# PLD_Connectors_PC-104.net
KiCad netlist of a schematic drawn in Altium Designer
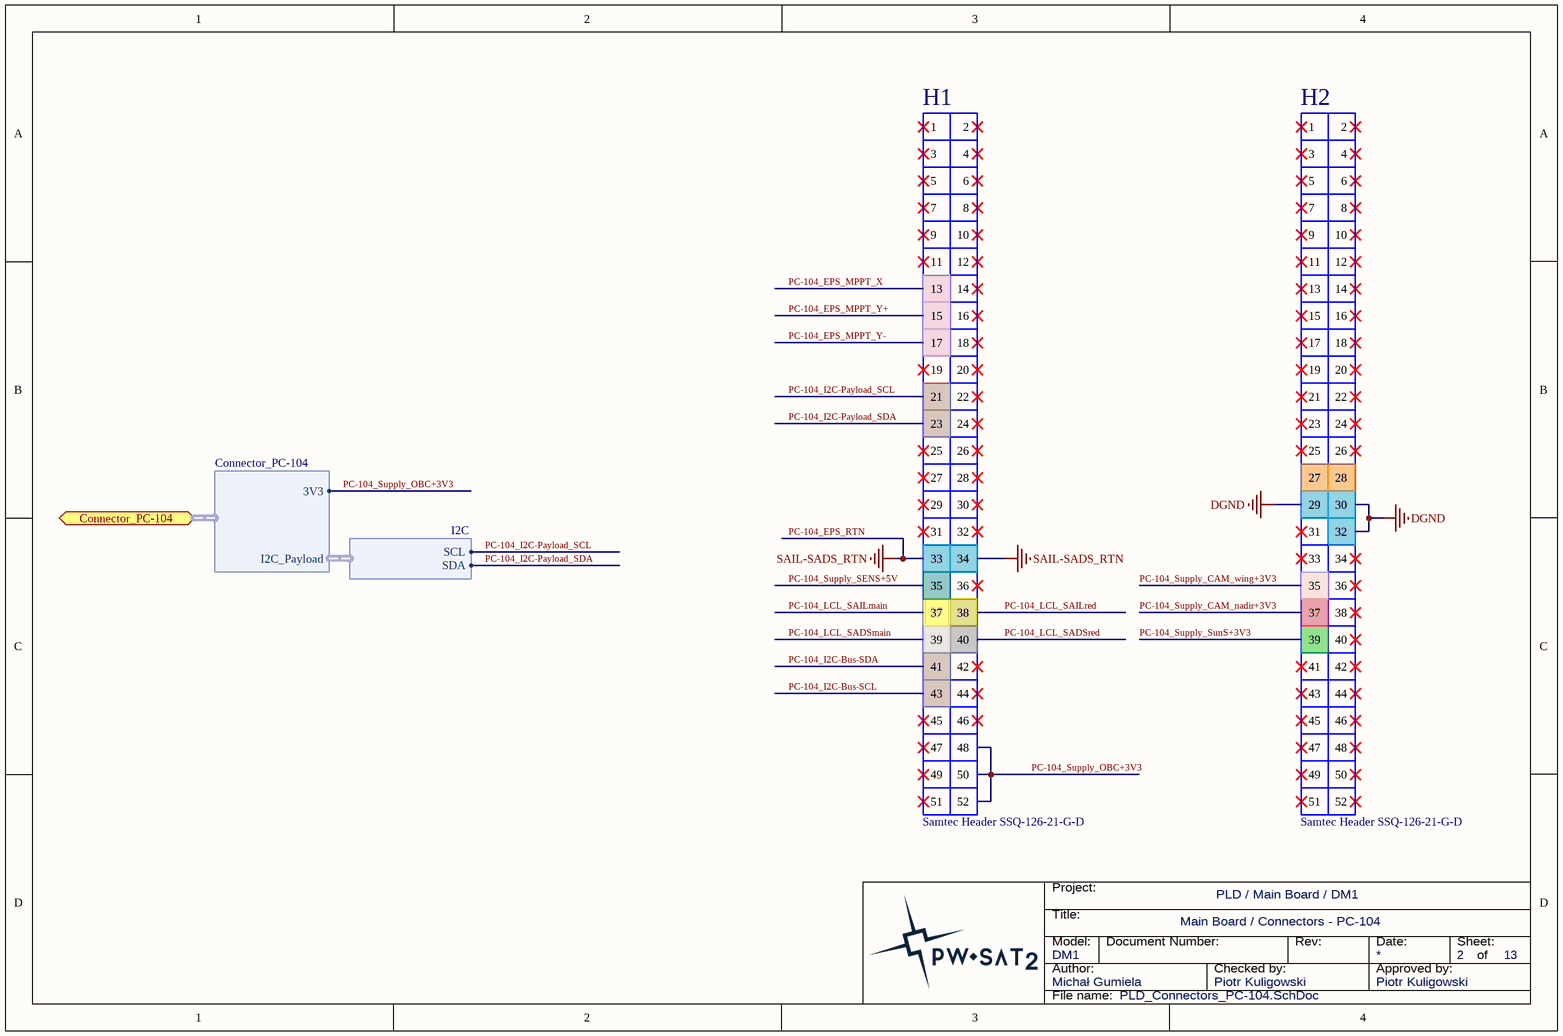
[diagram p0: PLD_Connectors_PC-104.SchDoc]

(export (version "E")
  (design (tool "Eeschema 10.0.6"))
  (components
    (comp (ref "H1")
      (value "Samtec Header SSQ-126-21-G-D")
      (footprint "Samtec_SSQ-126-21-G-D")
      (description "Samtec SSQ Series Header , 2.54mm pitch, 2x26pin. PC-104 Stack Connector.")
      (libsource (lib "connectors_printed-circuit-board") (part "Samtec_SSQ-126-xx-x-D"))
    )
    (comp (ref "H2")
      (value "Samtec Header SSQ-126-21-G-D")
      (footprint "Samtec_SSQ-126-21-G-D")
      (description "Samtec SSQ Series Header , 2.54mm pitch, 2x26pin. PC-104 Stack Connector.")
      (libsource (lib "connectors_printed-circuit-board") (part "Samtec_SSQ-126-xx-x-D"))
    )
  )
  (nets
    (net (code "4") (name "/PC-104_EPS_MPPT_X") (class "Default")
      (node (ref "H1") (pin "13") (pinfunction "13_13") (pintype "passive"))
    )
    (net (code "5") (name "/PC-104_EPS_MPPT_Y+") (class "Default")
      (node (ref "H1") (pin "15") (pinfunction "15_15") (pintype "passive"))
    )
    (net (code "6") (name "/PC-104_EPS_MPPT_Y-") (class "Default")
      (node (ref "H1") (pin "17") (pinfunction "17_17") (pintype "passive"))
    )
    (net (code "7") (name "/PC-104_I2C-Bus-SCL") (class "Default")
      (node (ref "H1") (pin "43") (pinfunction "43_43") (pintype "passive"))
    )
    (net (code "8") (name "/PC-104_I2C-Bus-SDA") (class "Default")
      (node (ref "H1") (pin "41") (pinfunction "41_41") (pintype "passive"))
    )
    (net (code "9") (name "/PC-104_I2C-Payload_SCL") (class "Default")
      (node (ref "H1") (pin "21") (pinfunction "21_21") (pintype "passive"))
    )
    (net (code "10") (name "/PC-104_I2C-Payload_SDA") (class "Default")
      (node (ref "H1") (pin "23") (pinfunction "23_23") (pintype "passive"))
    )
    (net (code "11") (name "/PC-104_LCL_SADSmain") (class "Default")
      (node (ref "H1") (pin "39") (pinfunction "39_39") (pintype "passive"))
    )
    (net (code "12") (name "/PC-104_LCL_SADSred") (class "Default")
      (node (ref "H1") (pin "40") (pinfunction "40_40") (pintype "passive"))
    )
    (net (code "13") (name "/PC-104_LCL_SAILmain") (class "Default")
      (node (ref "H1") (pin "37") (pinfunction "37_37") (pintype "passive"))
    )
    (net (code "14") (name "/PC-104_LCL_SAILred") (class "Default")
      (node (ref "H1") (pin "38") (pinfunction "38_38") (pintype "passive"))
    )
    (net (code "15") (name "/PC-104_Supply_CAM_nadir+3V3") (class "Default")
      (node (ref "H2") (pin "37") (pinfunction "37_37") (pintype "passive"))
    )
    (net (code "16") (name "/PC-104_Supply_CAM_wing+3V3") (class "Default")
      (node (ref "H2") (pin "35") (pinfunction "35_35") (pintype "passive"))
    )
    (net (code "17") (name "/PC-104_Supply_OBC+3V3") (class "Default")
      (node (ref "H1") (pin "48") (pinfunction "48_48") (pintype "passive"))
      (node (ref "H1") (pin "50") (pinfunction "50_50") (pintype "passive"))
      (node (ref "H1") (pin "52") (pinfunction "52_52") (pintype "passive"))
    )
    (net (code "18") (name "/PC-104_Supply_SENS+5V") (class "Default")
      (node (ref "H1") (pin "35") (pinfunction "35_35") (pintype "passive"))
    )
    (net (code "19") (name "/PC-104_Supply_SunS+3V3") (class "Default")
      (node (ref "H2") (pin "39") (pinfunction "39_39") (pintype "passive"))
    )
    (net (code "21") (name "DGND") (class "Default")
      (node (ref "H2") (pin "29") (pinfunction "29_29") (pintype "passive"))
      (node (ref "H2") (pin "30") (pinfunction "30_30") (pintype "passive"))
      (node (ref "H2") (pin "32") (pinfunction "32_32") (pintype "passive"))
    )
    (net (code "22") (name "SAIL-SADS_RTN") (class "Default")
      (node (ref "H1") (pin "33") (pinfunction "33_33") (pintype "passive"))
      (node (ref "H1") (pin "34") (pinfunction "34_34") (pintype "passive"))
    )
    (net (code "23") (name "unconnected-(H1-Pad1)") (class "Default")
      (node (ref "H1") (pin "1") (pinfunction "1_1") (pintype "passive+no_connect"))
    )
    (net (code "24") (name "unconnected-(H1-Pad2)") (class "Default")
      (node (ref "H1") (pin "2") (pinfunction "2_2") (pintype "passive+no_connect"))
    )
    (net (code "25") (name "unconnected-(H1-Pad3)") (class "Default")
      (node (ref "H1") (pin "3") (pinfunction "3_3") (pintype "passive+no_connect"))
    )
    (net (code "26") (name "unconnected-(H1-Pad4)") (class "Default")
      (node (ref "H1") (pin "4") (pinfunction "4_4") (pintype "passive+no_connect"))
    )
    (net (code "27") (name "unconnected-(H1-Pad5)") (class "Default")
      (node (ref "H1") (pin "5") (pinfunction "5_5") (pintype "passive+no_connect"))
    )
    (net (code "28") (name "unconnected-(H1-Pad6)") (class "Default")
      (node (ref "H1") (pin "6") (pinfunction "6_6") (pintype "passive+no_connect"))
    )
    (net (code "29") (name "unconnected-(H1-Pad7)") (class "Default")
      (node (ref "H1") (pin "7") (pinfunction "7_7") (pintype "passive+no_connect"))
    )
    (net (code "30") (name "unconnected-(H1-Pad8)") (class "Default")
      (node (ref "H1") (pin "8") (pinfunction "8_8") (pintype "passive+no_connect"))
    )
    (net (code "31") (name "unconnected-(H1-Pad9)") (class "Default")
      (node (ref "H1") (pin "9") (pinfunction "9_9") (pintype "passive+no_connect"))
    )
    (net (code "32") (name "unconnected-(H1-Pad10)") (class "Default")
      (node (ref "H1") (pin "10") (pinfunction "10_10") (pintype "passive+no_connect"))
    )
    (net (code "33") (name "unconnected-(H1-Pad11)") (class "Default")
      (node (ref "H1") (pin "11") (pinfunction "11_11") (pintype "passive+no_connect"))
    )
    (net (code "34") (name "unconnected-(H1-Pad12)") (class "Default")
      (node (ref "H1") (pin "12") (pinfunction "12_12") (pintype "passive+no_connect"))
    )
    (net (code "35") (name "unconnected-(H1-Pad14)") (class "Default")
      (node (ref "H1") (pin "14") (pinfunction "14_14") (pintype "passive+no_connect"))
    )
    (net (code "36") (name "unconnected-(H1-Pad16)") (class "Default")
      (node (ref "H1") (pin "16") (pinfunction "16_16") (pintype "passive+no_connect"))
    )
    (net (code "37") (name "unconnected-(H1-Pad18)") (class "Default")
      (node (ref "H1") (pin "18") (pinfunction "18_18") (pintype "passive+no_connect"))
    )
    (net (code "38") (name "unconnected-(H1-Pad19)") (class "Default")
      (node (ref "H1") (pin "19") (pinfunction "19_19") (pintype "passive+no_connect"))
    )
    (net (code "39") (name "unconnected-(H1-Pad20)") (class "Default")
      (node (ref "H1") (pin "20") (pinfunction "20_20") (pintype "passive+no_connect"))
    )
    (net (code "40") (name "unconnected-(H1-Pad22)") (class "Default")
      (node (ref "H1") (pin "22") (pinfunction "22_22") (pintype "passive+no_connect"))
    )
    (net (code "41") (name "unconnected-(H1-Pad24)") (class "Default")
      (node (ref "H1") (pin "24") (pinfunction "24_24") (pintype "passive+no_connect"))
    )
    (net (code "42") (name "unconnected-(H1-Pad25)") (class "Default")
      (node (ref "H1") (pin "25") (pinfunction "25_25") (pintype "passive+no_connect"))
    )
    (net (code "43") (name "unconnected-(H1-Pad26)") (class "Default")
      (node (ref "H1") (pin "26") (pinfunction "26_26") (pintype "passive+no_connect"))
    )
    (net (code "44") (name "unconnected-(H1-Pad27)") (class "Default")
      (node (ref "H1") (pin "27") (pinfunction "27_27") (pintype "passive+no_connect"))
    )
    (net (code "45") (name "unconnected-(H1-Pad28)") (class "Default")
      (node (ref "H1") (pin "28") (pinfunction "28_28") (pintype "passive+no_connect"))
    )
    (net (code "46") (name "unconnected-(H1-Pad29)") (class "Default")
      (node (ref "H1") (pin "29") (pinfunction "29_29") (pintype "passive+no_connect"))
    )
    (net (code "47") (name "unconnected-(H1-Pad30)") (class "Default")
      (node (ref "H1") (pin "30") (pinfunction "30_30") (pintype "passive+no_connect"))
    )
    (net (code "48") (name "unconnected-(H1-Pad31)") (class "Default")
      (node (ref "H1") (pin "31") (pinfunction "31_31") (pintype "passive+no_connect"))
    )
    (net (code "49") (name "unconnected-(H1-Pad32)") (class "Default")
      (node (ref "H1") (pin "32") (pinfunction "32_32") (pintype "passive+no_connect"))
    )
    (net (code "50") (name "unconnected-(H1-Pad36)") (class "Default")
      (node (ref "H1") (pin "36") (pinfunction "36_36") (pintype "passive+no_connect"))
    )
    (net (code "51") (name "unconnected-(H1-Pad42)") (class "Default")
      (node (ref "H1") (pin "42") (pinfunction "42_42") (pintype "passive+no_connect"))
    )
    (net (code "52") (name "unconnected-(H1-Pad44)") (class "Default")
      (node (ref "H1") (pin "44") (pinfunction "44_44") (pintype "passive+no_connect"))
    )
    (net (code "53") (name "unconnected-(H1-Pad45)") (class "Default")
      (node (ref "H1") (pin "45") (pinfunction "45_45") (pintype "passive+no_connect"))
    )
    (net (code "54") (name "unconnected-(H1-Pad46)") (class "Default")
      (node (ref "H1") (pin "46") (pinfunction "46_46") (pintype "passive+no_connect"))
    )
    (net (code "55") (name "unconnected-(H1-Pad47)") (class "Default")
      (node (ref "H1") (pin "47") (pinfunction "47_47") (pintype "passive+no_connect"))
    )
    (net (code "56") (name "unconnected-(H1-Pad49)") (class "Default")
      (node (ref "H1") (pin "49") (pinfunction "49_49") (pintype "passive+no_connect"))
    )
    (net (code "57") (name "unconnected-(H1-Pad51)") (class "Default")
      (node (ref "H1") (pin "51") (pinfunction "51_51") (pintype "passive+no_connect"))
    )
    (net (code "58") (name "unconnected-(H2-Pad1)") (class "Default")
      (node (ref "H2") (pin "1") (pinfunction "1_1") (pintype "passive+no_connect"))
    )
    (net (code "59") (name "unconnected-(H2-Pad2)") (class "Default")
      (node (ref "H2") (pin "2") (pinfunction "2_2") (pintype "passive+no_connect"))
    )
    (net (code "60") (name "unconnected-(H2-Pad3)") (class "Default")
      (node (ref "H2") (pin "3") (pinfunction "3_3") (pintype "passive+no_connect"))
    )
    (net (code "61") (name "unconnected-(H2-Pad4)") (class "Default")
      (node (ref "H2") (pin "4") (pinfunction "4_4") (pintype "passive+no_connect"))
    )
    (net (code "62") (name "unconnected-(H2-Pad5)") (class "Default")
      (node (ref "H2") (pin "5") (pinfunction "5_5") (pintype "passive+no_connect"))
    )
    (net (code "63") (name "unconnected-(H2-Pad6)") (class "Default")
      (node (ref "H2") (pin "6") (pinfunction "6_6") (pintype "passive+no_connect"))
    )
    (net (code "64") (name "unconnected-(H2-Pad7)") (class "Default")
      (node (ref "H2") (pin "7") (pinfunction "7_7") (pintype "passive+no_connect"))
    )
    (net (code "65") (name "unconnected-(H2-Pad8)") (class "Default")
      (node (ref "H2") (pin "8") (pinfunction "8_8") (pintype "passive+no_connect"))
    )
    (net (code "66") (name "unconnected-(H2-Pad9)") (class "Default")
      (node (ref "H2") (pin "9") (pinfunction "9_9") (pintype "passive+no_connect"))
    )
    (net (code "67") (name "unconnected-(H2-Pad10)") (class "Default")
      (node (ref "H2") (pin "10") (pinfunction "10_10") (pintype "passive+no_connect"))
    )
    (net (code "68") (name "unconnected-(H2-Pad11)") (class "Default")
      (node (ref "H2") (pin "11") (pinfunction "11_11") (pintype "passive+no_connect"))
    )
    (net (code "69") (name "unconnected-(H2-Pad12)") (class "Default")
      (node (ref "H2") (pin "12") (pinfunction "12_12") (pintype "passive+no_connect"))
    )
    (net (code "70") (name "unconnected-(H2-Pad13)") (class "Default")
      (node (ref "H2") (pin "13") (pinfunction "13_13") (pintype "passive+no_connect"))
    )
    (net (code "71") (name "unconnected-(H2-Pad14)") (class "Default")
      (node (ref "H2") (pin "14") (pinfunction "14_14") (pintype "passive+no_connect"))
    )
    (net (code "72") (name "unconnected-(H2-Pad15)") (class "Default")
      (node (ref "H2") (pin "15") (pinfunction "15_15") (pintype "passive+no_connect"))
    )
    (net (code "73") (name "unconnected-(H2-Pad16)") (class "Default")
      (node (ref "H2") (pin "16") (pinfunction "16_16") (pintype "passive+no_connect"))
    )
    (net (code "74") (name "unconnected-(H2-Pad17)") (class "Default")
      (node (ref "H2") (pin "17") (pinfunction "17_17") (pintype "passive+no_connect"))
    )
    (net (code "75") (name "unconnected-(H2-Pad18)") (class "Default")
      (node (ref "H2") (pin "18") (pinfunction "18_18") (pintype "passive+no_connect"))
    )
    (net (code "76") (name "unconnected-(H2-Pad19)") (class "Default")
      (node (ref "H2") (pin "19") (pinfunction "19_19") (pintype "passive+no_connect"))
    )
    (net (code "77") (name "unconnected-(H2-Pad20)") (class "Default")
      (node (ref "H2") (pin "20") (pinfunction "20_20") (pintype "passive+no_connect"))
    )
    (net (code "78") (name "unconnected-(H2-Pad21)") (class "Default")
      (node (ref "H2") (pin "21") (pinfunction "21_21") (pintype "passive+no_connect"))
    )
    (net (code "79") (name "unconnected-(H2-Pad22)") (class "Default")
      (node (ref "H2") (pin "22") (pinfunction "22_22") (pintype "passive+no_connect"))
    )
    (net (code "80") (name "unconnected-(H2-Pad23)") (class "Default")
      (node (ref "H2") (pin "23") (pinfunction "23_23") (pintype "passive+no_connect"))
    )
    (net (code "81") (name "unconnected-(H2-Pad24)") (class "Default")
      (node (ref "H2") (pin "24") (pinfunction "24_24") (pintype "passive+no_connect"))
    )
    (net (code "82") (name "unconnected-(H2-Pad25)") (class "Default")
      (node (ref "H2") (pin "25") (pinfunction "25_25") (pintype "passive+no_connect"))
    )
    (net (code "83") (name "unconnected-(H2-Pad26)") (class "Default")
      (node (ref "H2") (pin "26") (pinfunction "26_26") (pintype "passive+no_connect"))
    )
    (net (code "84") (name "unconnected-(H2-Pad27)") (class "Default")
      (node (ref "H2") (pin "27") (pinfunction "27_27") (pintype "passive"))
    )
    (net (code "85") (name "unconnected-(H2-Pad28)") (class "Default")
      (node (ref "H2") (pin "28") (pinfunction "28_28") (pintype "passive"))
    )
    (net (code "86") (name "unconnected-(H2-Pad31)") (class "Default")
      (node (ref "H2") (pin "31") (pinfunction "31_31") (pintype "passive+no_connect"))
    )
    (net (code "87") (name "unconnected-(H2-Pad33)") (class "Default")
      (node (ref "H2") (pin "33") (pinfunction "33_33") (pintype "passive+no_connect"))
    )
    (net (code "88") (name "unconnected-(H2-Pad34)") (class "Default")
      (node (ref "H2") (pin "34") (pinfunction "34_34") (pintype "passive+no_connect"))
    )
    (net (code "89") (name "unconnected-(H2-Pad36)") (class "Default")
      (node (ref "H2") (pin "36") (pinfunction "36_36") (pintype "passive+no_connect"))
    )
    (net (code "90") (name "unconnected-(H2-Pad38)") (class "Default")
      (node (ref "H2") (pin "38") (pinfunction "38_38") (pintype "passive+no_connect"))
    )
    (net (code "91") (name "unconnected-(H2-Pad40)") (class "Default")
      (node (ref "H2") (pin "40") (pinfunction "40_40") (pintype "passive+no_connect"))
    )
    (net (code "92") (name "unconnected-(H2-Pad41)") (class "Default")
      (node (ref "H2") (pin "41") (pinfunction "41_41") (pintype "passive+no_connect"))
    )
    (net (code "93") (name "unconnected-(H2-Pad42)") (class "Default")
      (node (ref "H2") (pin "42") (pinfunction "42_42") (pintype "passive+no_connect"))
    )
    (net (code "94") (name "unconnected-(H2-Pad43)") (class "Default")
      (node (ref "H2") (pin "43") (pinfunction "43_43") (pintype "passive+no_connect"))
    )
    (net (code "95") (name "unconnected-(H2-Pad44)") (class "Default")
      (node (ref "H2") (pin "44") (pinfunction "44_44") (pintype "passive+no_connect"))
    )
    (net (code "96") (name "unconnected-(H2-Pad45)") (class "Default")
      (node (ref "H2") (pin "45") (pinfunction "45_45") (pintype "passive+no_connect"))
    )
    (net (code "97") (name "unconnected-(H2-Pad46)") (class "Default")
      (node (ref "H2") (pin "46") (pinfunction "46_46") (pintype "passive+no_connect"))
    )
    (net (code "98") (name "unconnected-(H2-Pad47)") (class "Default")
      (node (ref "H2") (pin "47") (pinfunction "47_47") (pintype "passive+no_connect"))
    )
    (net (code "99") (name "unconnected-(H2-Pad48)") (class "Default")
      (node (ref "H2") (pin "48") (pinfunction "48_48") (pintype "passive+no_connect"))
    )
    (net (code "100") (name "unconnected-(H2-Pad49)") (class "Default")
      (node (ref "H2") (pin "49") (pinfunction "49_49") (pintype "passive+no_connect"))
    )
    (net (code "101") (name "unconnected-(H2-Pad50)") (class "Default")
      (node (ref "H2") (pin "50") (pinfunction "50_50") (pintype "passive+no_connect"))
    )
    (net (code "102") (name "unconnected-(H2-Pad51)") (class "Default")
      (node (ref "H2") (pin "51") (pinfunction "51_51") (pintype "passive+no_connect"))
    )
    (net (code "103") (name "unconnected-(H2-Pad52)") (class "Default")
      (node (ref "H2") (pin "52") (pinfunction "52_52") (pintype "passive+no_connect"))
    )
  )
)
